# USB.net
KiCad netlist of a schematic drawn in Altium Designer
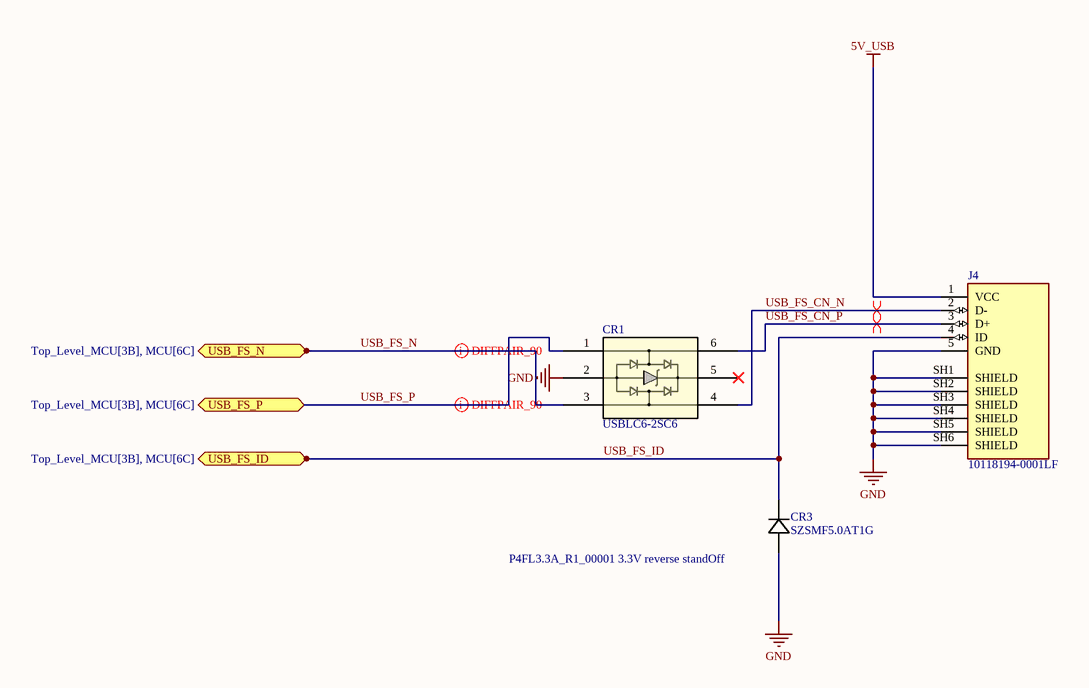
[diagram p0: USB.SchDoc]

(export (version "E")
  (design (tool "Eeschema 10.0.6"))
  (components
    (comp (ref "CR1")
      (value "USBLC6-2SC6")
      (footprint "SOT23-6L_STM")
      (description "ESD Protection for USB 2.0 High Speed")
      (fields (field (name "COPYRIGHT") "Copyright (C) 2025 Ultra Librarian. All rights reserved."))
      (libsource (lib "USBLC6-2SC6") (part "USBLC6-2SC6"))
    )
    (comp (ref "CR3")
      (value "SZSMF5.0AT1G")
      (footprint "CR_SZSMF_LTF")
      (description "Description")
      (fields (field (name "COPYRIGHT") "Copyright (C) 2025 Ultra Librarian. All rights reserved."))
      (libsource (lib "SZSMF5P0AT1G") (part "SZSMF5.0AT1G"))
    )
    (comp (ref "J4")
      (value "10118194-0001LF")
      (footprint "AMPHENOL_10118194-0001LF")
      (description "Micro USB, Input Output Connectors, B TYPE RECEPTACLE with flange")
      (fields (field (name "MF") "Amphenol ICC"))
      (libsource (lib "10118194-0001LF") (part "10118194-0001LF"))
    )
  )
  (nets
    (net (code "1") (name "/USB_FS_CN_N") (class "Default")
      (node (ref "CR1") (pin "4") (pinfunction "4_4") (pintype "passive"))
      (node (ref "J4") (pin "2") (pinfunction "D-_2") (pintype "bidirectional"))
    )
    (net (code "2") (name "/USB_FS_CN_P") (class "Default")
      (node (ref "CR1") (pin "6") (pinfunction "6_6") (pintype "passive"))
      (node (ref "J4") (pin "3") (pinfunction "D+_3") (pintype "bidirectional"))
    )
    (net (code "3") (name "/USB_FS_ID") (class "Default")
      (node (ref "CR3") (pin "1") (pinfunction "1_1") (pintype "passive"))
      (node (ref "J4") (pin "4") (pinfunction "ID_4") (pintype "bidirectional"))
    )
    (net (code "4") (name "/USB_FS_N") (class "Default")
      (node (ref "CR1") (pin "3") (pinfunction "3_3") (pintype "passive"))
    )
    (net (code "5") (name "/USB_FS_P") (class "Default")
      (node (ref "CR1") (pin "1") (pinfunction "1_1") (pintype "passive"))
    )
    (net (code "6") (name "5V_USB") (class "Default")
      (node (ref "J4") (pin "1") (pinfunction "VCC_1") (pintype "power_in"))
    )
    (net (code "7") (name "GND") (class "Default")
      (node (ref "CR1") (pin "2") (pinfunction "2_2") (pintype "passive"))
      (node (ref "CR3") (pin "2") (pinfunction "2_2") (pintype "passive"))
      (node (ref "J4") (pin "5") (pinfunction "GND_5") (pintype "power_in"))
      (node (ref "J4") (pin "SH1") (pinfunction "SHIELD_SH1") (pintype "passive"))
      (node (ref "J4") (pin "SH2") (pinfunction "SHIELD_SH2") (pintype "passive"))
      (node (ref "J4") (pin "SH3") (pinfunction "SHIELD_SH3") (pintype "passive"))
      (node (ref "J4") (pin "SH4") (pinfunction "SHIELD_SH4") (pintype "passive"))
      (node (ref "J4") (pin "SH5") (pinfunction "SHIELD_SH5") (pintype "passive"))
      (node (ref "J4") (pin "SH6") (pinfunction "SHIELD_SH6") (pintype "passive"))
    )
    (net (code "8") (name "unconnected-(CR1-Pad5)") (class "Default")
      (node (ref "CR1") (pin "5") (pinfunction "5_5") (pintype "passive+no_connect"))
    )
  )
)
